# PE0024.net
KiCad netlist of a schematic drawn in Altium Designer
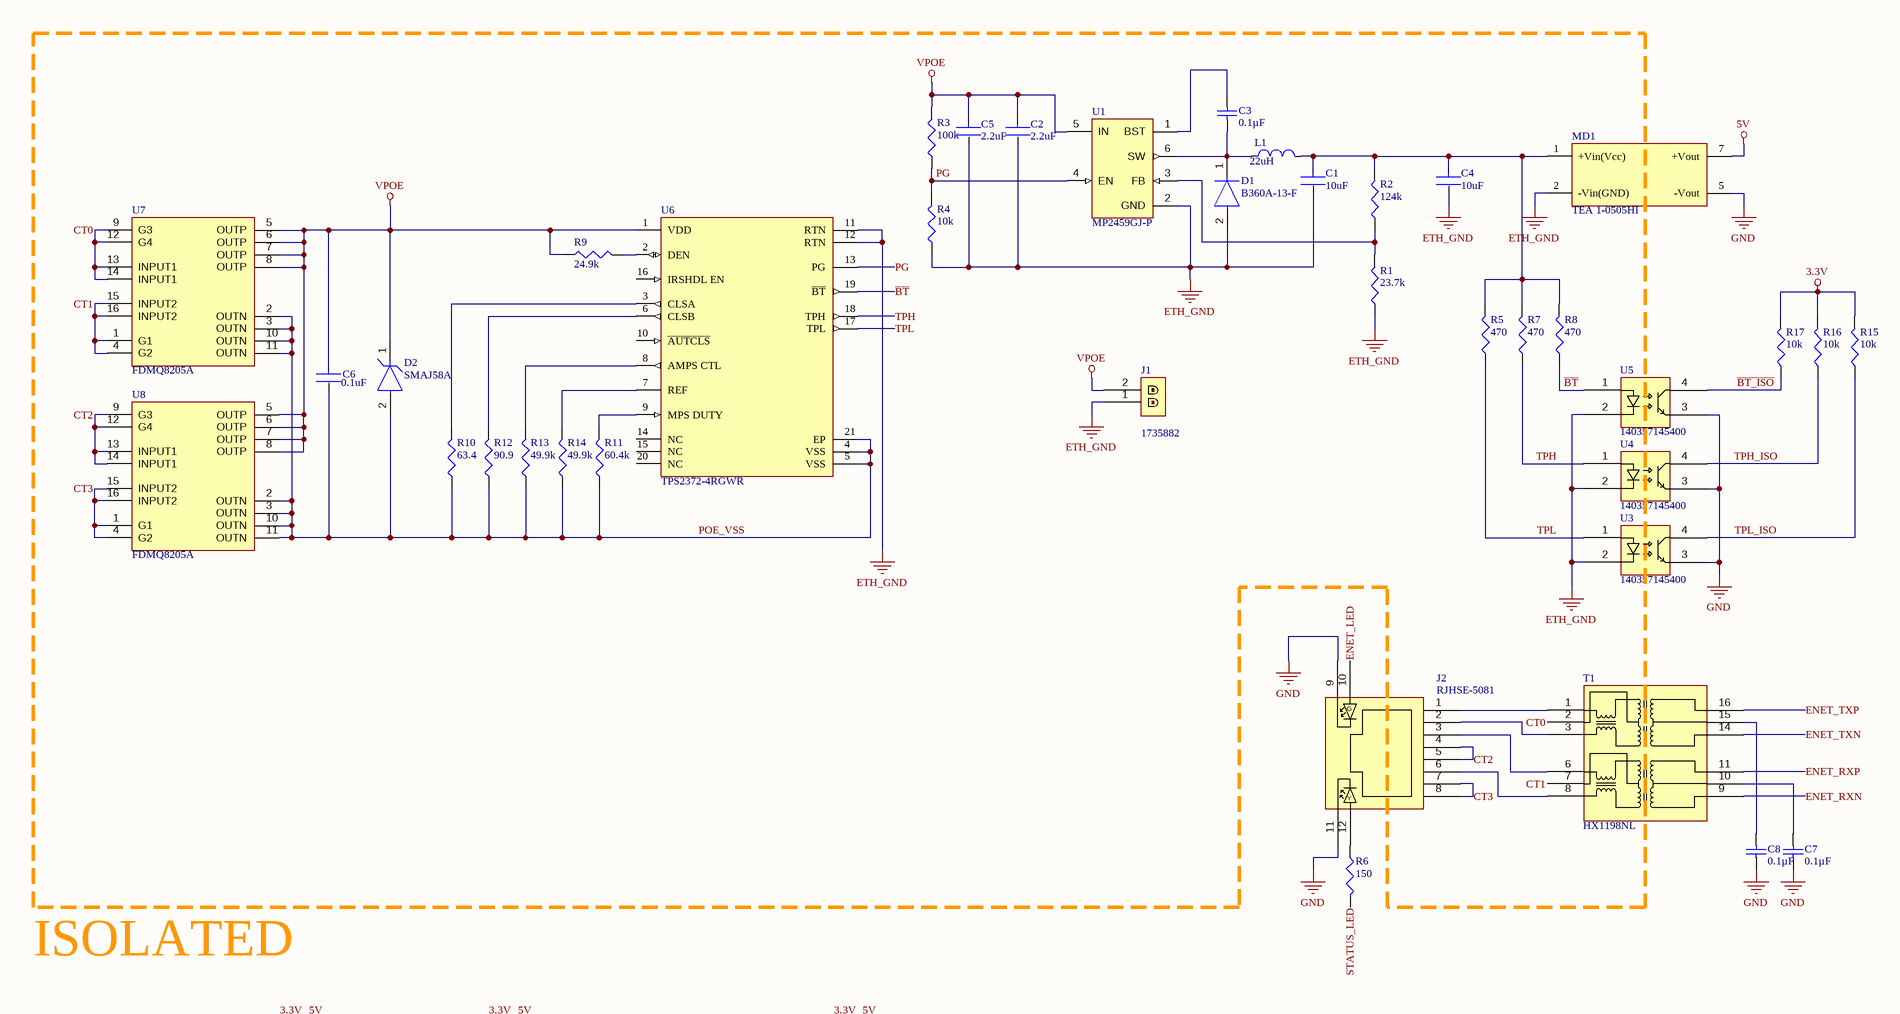
[diagram p0: PE0024.SchDoc, top left]
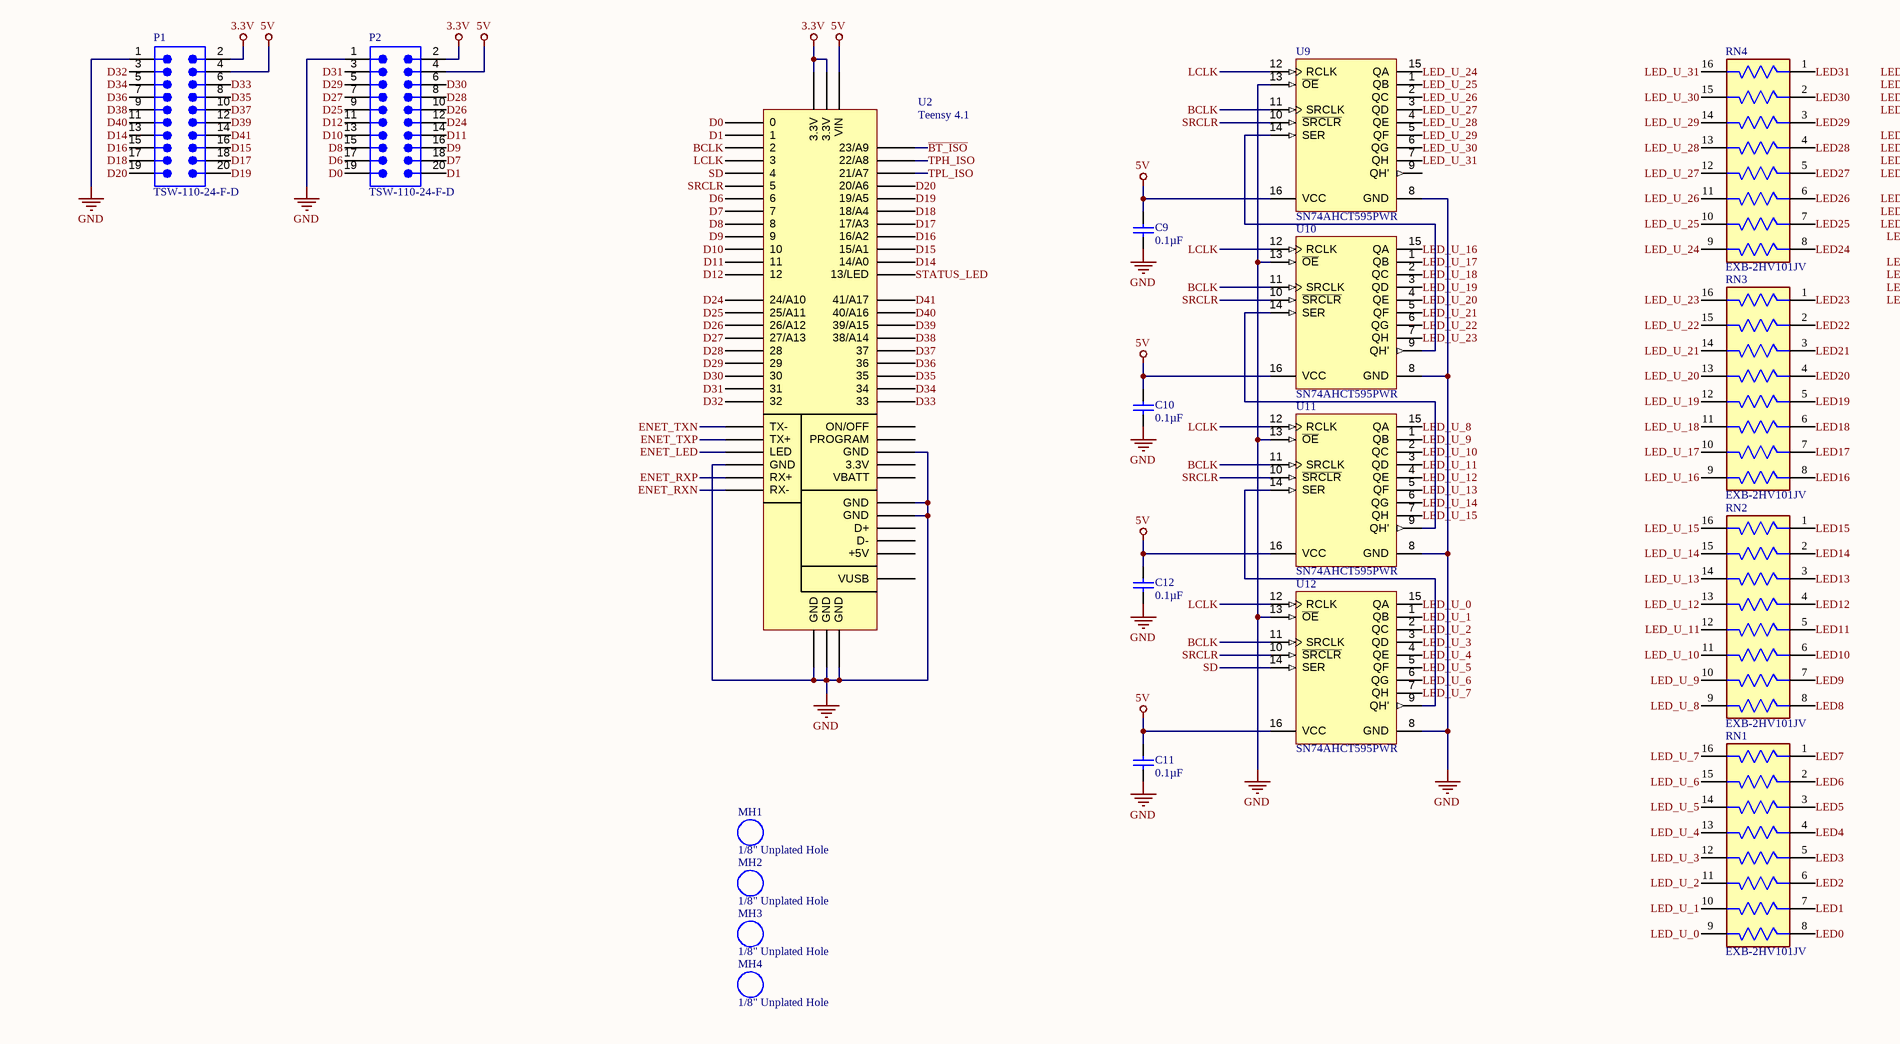
[diagram p1: PE0024.SchDoc, bottom left]
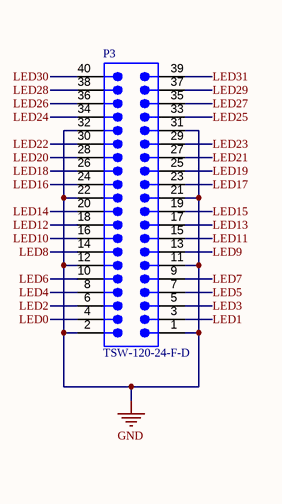
[diagram p2: PE0024.SchDoc, bottom right]

(export (version "E")
  (design (tool "Eeschema 10.0.6"))
  (components
    (comp (ref "C1")
      (value "GRM21BR61C106KE15L")
      (footprint "FP-GRM21B-0_1-IPC_C")
      (description "Chip Multilayer Ceramic Capacitors for General Purpose, 0805, 10uF, X5R, 15%, 10%, 16V")
      (fields
        (field (name "TOLERANCE") "10%")
        (field (name "VOLTAGE") "16V")
        (field (name "CAPACITANCE") "10uF")
      )
      (libsource (lib "Altium Content Vault") (part "b4654b650e69147ec39a6b967a45e02"))
    )
    (comp (ref "C2")
      (value "C3216X7S2A225K160AB")
      (footprint "FP-C3216-160-0_2-IPC_B")
      (description "Multilayer Ceramic Capacitors 2.2uF ±10% 100V X7S SMD 1206")
      (fields
        (field (name "TOLERANCE") "10%")
        (field (name "CAPACITANCE") "2.2uF")
        (field (name "VOLTAGE") "100V")
      )
      (libsource (lib "Altium Content Vault") (part "11868f565c42a9108669ba33697ecf6"))
    )
    (comp (ref "C3")
      (value "0.1µF")
      (footprint "0402CAP")
      (description "CAP CER 0.1UF 50V X7S 0402")
      (fields
        (field (name "PART NUMBER") "CAP_MUR_GRM155C71H104JE19D")
        (field (name "MANUFACTURER PART NUMBER") "GRM155C71H104JE19D")
        (field (name "PUBLISHER") "Altium Limited")
      )
      (libsource (lib "muRata_0402$") (part "CAP_MUR_GRM155C71H104JE19D"))
    )
    (comp (ref "C4")
      (value "GRM21BR61C106KE15L")
      (footprint "FP-GRM21B-0_1-IPC_C")
      (description "Chip Multilayer Ceramic Capacitors for General Purpose, 0805, 10uF, X5R, 15%, 10%, 16V")
      (fields
        (field (name "TOLERANCE") "10%")
        (field (name "VOLTAGE") "16V")
        (field (name "CAPACITANCE") "10uF")
      )
      (libsource (lib "Altium Content Vault") (part "b4654b650e69147ec39a6b967a45e02"))
    )
    (comp (ref "C5")
      (value "C3216X7S2A225K160AB")
      (footprint "FP-C3216-160-0_2-IPC_B")
      (description "Multilayer Ceramic Capacitors 2.2uF ±10% 100V X7S SMD 1206")
      (fields
        (field (name "TOLERANCE") "10%")
        (field (name "CAPACITANCE") "2.2uF")
        (field (name "VOLTAGE") "100V")
      )
      (libsource (lib "Altium Content Vault") (part "11868f565c42a9108669ba33697ecf6"))
    )
    (comp (ref "C6")
      (value "GRM188R72A104KA35D")
      (footprint "FP-GRM188-0_1-e0_2_0_5-IPC_B")
      (description "Chip Multilayer Ceramic Capacitors for General Purpose, 0603, 0.10uF, X7R, 15%, 10%, 100V")
      (fields
        (field (name "CAPACITANCE") "0.1uF")
        (field (name "VOLTAGE") "100V")
        (field (name "TOLERANCE") "10%")
      )
      (libsource (lib "Altium Content Vault") (part "11868f565c42a9108669ba33697ecf6"))
    )
    (comp (ref "C7")
      (value "0.1µF")
      (footprint "0402CAP")
      (description "CAP CER 0.1UF 50V X7S 0402")
      (fields
        (field (name "PART NUMBER") "CAP_MUR_GRM155C71H104JE19D")
        (field (name "MANUFACTURER PART NUMBER") "GRM155C71H104JE19D")
        (field (name "PUBLISHER") "Altium Limited")
      )
      (libsource (lib "muRata_0402$") (part "CAP_MUR_GRM155C71H104JE19D"))
    )
    (comp (ref "C8")
      (value "0.1µF")
      (footprint "0402CAP")
      (description "CAP CER 0.1UF 50V X7S 0402")
      (fields
        (field (name "PART NUMBER") "CAP_MUR_GRM155C71H104JE19D")
        (field (name "MANUFACTURER PART NUMBER") "GRM155C71H104JE19D")
        (field (name "PUBLISHER") "Altium Limited")
      )
      (libsource (lib "muRata_0402$") (part "CAP_MUR_GRM155C71H104JE19D"))
    )
    (comp (ref "C9")
      (value "0.1µF")
      (footprint "0402CAP")
      (description "CAP CER 0.1UF 50V X7S 0402")
      (fields
        (field (name "PART NUMBER") "CAP_MUR_GRM155C71H104JE19D")
        (field (name "MANUFACTURER PART NUMBER") "GRM155C71H104JE19D")
        (field (name "PUBLISHER") "Altium Limited")
      )
      (libsource (lib "muRata_0402$") (part "CAP_MUR_GRM155C71H104JE19D"))
    )
    (comp (ref "C10")
      (value "0.1µF")
      (footprint "0402CAP")
      (description "CAP CER 0.1UF 50V X7S 0402")
      (fields
        (field (name "PART NUMBER") "CAP_MUR_GRM155C71H104JE19D")
        (field (name "MANUFACTURER PART NUMBER") "GRM155C71H104JE19D")
        (field (name "PUBLISHER") "Altium Limited")
      )
      (libsource (lib "muRata_0402$") (part "CAP_MUR_GRM155C71H104JE19D"))
    )
    (comp (ref "C11")
      (value "0.1µF")
      (footprint "0402CAP")
      (description "CAP CER 0.1UF 50V X7S 0402")
      (fields
        (field (name "PART NUMBER") "CAP_MUR_GRM155C71H104JE19D")
        (field (name "MANUFACTURER PART NUMBER") "GRM155C71H104JE19D")
        (field (name "PUBLISHER") "Altium Limited")
      )
      (libsource (lib "muRata_0402$") (part "CAP_MUR_GRM155C71H104JE19D"))
    )
    (comp (ref "C12")
      (value "0.1µF")
      (footprint "0402CAP")
      (description "CAP CER 0.1UF 50V X7S 0402")
      (fields
        (field (name "PART NUMBER") "CAP_MUR_GRM155C71H104JE19D")
        (field (name "MANUFACTURER PART NUMBER") "GRM155C71H104JE19D")
        (field (name "PUBLISHER") "Altium Limited")
      )
      (libsource (lib "muRata_0402$") (part "CAP_MUR_GRM155C71H104JE19D"))
    )
    (comp (ref "D1")
      (value "B360A-13-F")
      (footprint "FP-SMA-MFG")
      (description "DIODE SCHOTTKY 60V 3A SMA")
      (libsource (lib "Altium Content Vault") (part "d7152d700b627762746794eb795d46e"))
    )
    (comp (ref "D2")
      (value "SMAJ58A")
      (footprint "FP-SMAJ-MFG")
      (description "TVS DIODE 58V 93.6V DO214AC")
      (fields (field (name "VOLTAGE") "58V"))
      (libsource (lib "Altium Content Vault") (part "f813f71cba58e380607f5dd3caf9714"))
    )
    (comp (ref "J1")
      (value "1735882")
      (footprint "MSTBW 2,5/2-G-5,08")
      (description "Pluggable Terminal Blocks 2 Pos 5.08mm pitch Through Hole Header")
      (fields
        (field (name "MANUFACTURER") "Phoenix Contact")
        (field (name "VOLTAGE") "300V")
        (field (name "MANUFACTURER PART NUMBER") "1735882")
      )
      (libsource (lib "RDS") (part "1735882"))
    )
    (comp (ref "J2")
      (value "RJHSE-5081")
      (footprint "RDS:RJHSE-5081")
      (description "Modular Jack - Right Angle, Input Output Connectors 8P8C, RA, Without Shield, With LEDs.")
      (fields (field (name "MANUFACTURER") "Amphenol") (field (name "MANUFACTURER PART NUMBER") "RJHSE-5081"))
      (libsource (lib "RDS") (part "RJHSE-5081"))
    )
    (comp (ref "L1")
      (value "NRS6028T220MMGJ")
      (footprint "FP-NR6028-MFG")
      (description "SMD Power Inductors 22uH ±20% 1.3A 0.1755Ω")
      (fields (field (name "INDUCTANCE") "22uH") (field (name "TOLERANCE") "20%"))
      (libsource (lib "Altium Content Vault") (part "725321dda6339637d4d059423bc1c3c"))
    )
    (comp (ref "MD1")
      (value "TEA 1-0505HI")
      (footprint "FP-TEA_1HI-MFG")
      (description "DC DC CONVERTER 5V 1W")
      (libsource (lib "Altium Content Vault") (part "4f7ce3a56b2658afe72e2cdf5ebd808"))
    )
    (comp (ref "MH1")
      (value "1/8\" Unplated Hole")
      (footprint "1/8\" Unplated Hole")
      (libsource (lib "RDS") (part "1/8{dblquote} Unplated Hole"))
    )
    (comp (ref "MH2")
      (value "1/8\" Unplated Hole")
      (footprint "1/8\" Unplated Hole")
      (libsource (lib "RDS") (part "1/8{dblquote} Unplated Hole"))
    )
    (comp (ref "MH3")
      (value "1/8\" Unplated Hole")
      (footprint "1/8\" Unplated Hole")
      (libsource (lib "RDS") (part "1/8{dblquote} Unplated Hole"))
    )
    (comp (ref "MH4")
      (value "1/8\" Unplated Hole")
      (footprint "1/8\" Unplated Hole")
      (libsource (lib "RDS") (part "1/8{dblquote} Unplated Hole"))
    )
    (comp (ref "P1")
      (value "TSW-110-24-F-D")
      (footprint "SMTC-TSW-110-24-X-D")
      (description "0.025\" SQ Post Header, Through-hole, Vertical, -55 to 125 degC, 2.54 mm Pitch, 20-Pin, Male, RoHS")
      (fields (field (name "MANUFACTURER") "Samtec"))
      (libsource (lib "RDS") (part "CMP-1024-00453-1"))
    )
    (comp (ref "P2")
      (value "TSW-110-24-F-D")
      (footprint "SMTC-TSW-110-24-X-D")
      (description "0.025\" SQ Post Header, Through-hole, Vertical, -55 to 125 degC, 2.54 mm Pitch, 20-Pin, Male, RoHS")
      (fields (field (name "MANUFACTURER") "Samtec"))
      (libsource (lib "RDS") (part "CMP-1024-00453-1"))
    )
    (comp (ref "P3")
      (value "TSW-120-24-F-D")
      (footprint "SMTC-TSW-120-24-X-D")
      (description "0.025\" SQ Post Header, Through-hole, Vertical, -55 to 125 degC, 2.54 mm Pitch, 40-Pin, Male, RoHS")
      (fields (field (name "MANUFACTURER") "Samtec"))
      (libsource (lib "Altium Content Vault") (part "SMTC-TSW-120-X-X-D-X"))
    )
    (comp (ref "R1")
      (value "23.7k")
      (footprint "0402RES")
      (description "RES SMD 23.7K OHM 1% 1/10W 0402")
      (fields
        (field (name "PART NUMBER") "RES_PAN_ERJ-2RKF2372X")
        (field (name "MANUFACTURER PART NUMBER") "ERJ-2RKF2372X")
        (field (name "PUBLISHER") "Altium Limited")
      )
      (libsource (lib "ERJ-2RKF$") (part "RES_PAN_ERJ-2RKF2372X"))
    )
    (comp (ref "R2")
      (value "124k")
      (footprint "0402RES")
      (description "RES SMD 124K OHM 1% 1/10W 0402")
      (fields
        (field (name "PART NUMBER") "RES_PAN_ERJ-2RKF1243X")
        (field (name "MANUFACTURER PART NUMBER") "ERJ-2RKF1243X")
        (field (name "PUBLISHER") "Altium Limited")
      )
      (libsource (lib "ERJ-2RKF$") (part "RES_PAN_ERJ-2RKF1243X"))
    )
    (comp (ref "R3")
      (value "100k")
      (footprint "0402RES")
      (description "RES SMD 100K OHM 1% 1/10W 0402")
      (fields
        (field (name "PART NUMBER") "RES_PAN_ERJ-2RKF1003X")
        (field (name "MANUFACTURER PART NUMBER") "ERJ-2RKF1003X")
        (field (name "PUBLISHER") "Altium Limited")
      )
      (libsource (lib "ERJ-2RKF$") (part "RES_PAN_ERJ-2RKF1003X"))
    )
    (comp (ref "R4")
      (value "10k")
      (footprint "0402RES")
      (description "RES SMD 10K OHM 1% 1/10W 0402")
      (fields
        (field (name "PART NUMBER") "RES_PAN_ERJ-2RKF1002X")
        (field (name "MANUFACTURER PART NUMBER") "ERJ-2RKF1002X")
        (field (name "PUBLISHER") "Altium Limited")
      )
      (libsource (lib "ERJ-2RKF$") (part "RES_PAN_ERJ-2RKF1002X"))
    )
    (comp (ref "R5")
      (value "470")
      (footprint "0402RES")
      (description "RES SMD 470 OHM 1% 1/10W 0402")
      (fields
        (field (name "PART NUMBER") "RES_PAN_ERJ-2RKF4700X")
        (field (name "MANUFACTURER PART NUMBER") "ERJ-2RKF4700X")
        (field (name "PUBLISHER") "Altium Limited")
      )
      (libsource (lib "ERJ-2RKF$") (part "RES_PAN_ERJ-2RKF4700X"))
    )
    (comp (ref "R6")
      (value "150")
      (footprint "0402RES")
      (description "RES SMD 150 OHM 1% 1/10W 0402")
      (fields
        (field (name "PART NUMBER") "RES_PAN_ERJ-2RKF1500X")
        (field (name "MANUFACTURER PART NUMBER") "ERJ-2RKF1500X")
        (field (name "PUBLISHER") "Altium Limited")
      )
      (libsource (lib "ERJ-2RKF$") (part "RES_PAN_ERJ-2RKF1500X"))
    )
    (comp (ref "R7")
      (value "470")
      (footprint "0402RES")
      (description "RES SMD 470 OHM 1% 1/10W 0402")
      (fields
        (field (name "PART NUMBER") "RES_PAN_ERJ-2RKF4700X")
        (field (name "MANUFACTURER PART NUMBER") "ERJ-2RKF4700X")
        (field (name "PUBLISHER") "Altium Limited")
      )
      (libsource (lib "ERJ-2RKF$") (part "RES_PAN_ERJ-2RKF4700X"))
    )
    (comp (ref "R8")
      (value "470")
      (footprint "0402RES")
      (description "RES SMD 470 OHM 1% 1/10W 0402")
      (fields
        (field (name "PART NUMBER") "RES_PAN_ERJ-2RKF4700X")
        (field (name "MANUFACTURER PART NUMBER") "ERJ-2RKF4700X")
        (field (name "PUBLISHER") "Altium Limited")
      )
      (libsource (lib "ERJ-2RKF$") (part "RES_PAN_ERJ-2RKF4700X"))
    )
    (comp (ref "R9")
      (value "24.9k")
      (footprint "0402RES")
      (description "RES SMD 24.9K OHM 1% 1/10W 0402")
      (fields
        (field (name "PART NUMBER") "RES_PAN_ERJ-2RKF2492X")
        (field (name "MANUFACTURER PART NUMBER") "ERJ-2RKF2492X")
        (field (name "PUBLISHER") "Altium Limited")
      )
      (libsource (lib "ERJ-2RKF$") (part "RES_PAN_ERJ-2RKF2492X"))
    )
    (comp (ref "R10")
      (value "63.4")
      (footprint "0402RES")
      (description "RES SMD 63.4 OHM 1% 1/10W 0402")
      (fields
        (field (name "PART NUMBER") "RES_PAN_ERJ-2RKF63R4X")
        (field (name "MANUFACTURER PART NUMBER") "ERJ-2RKF63R4X")
        (field (name "PUBLISHER") "Altium Limited")
      )
      (libsource (lib "ERJ-2RKF$") (part "RES_PAN_ERJ-2RKF63R4X"))
    )
    (comp (ref "R11")
      (value "60.4k")
      (footprint "0402RES")
      (description "RES SMD 60.4K OHM 1% 1/10W 0402")
      (fields
        (field (name "PART NUMBER") "RES_PAN_ERJ-2RKF6042X")
        (field (name "MANUFACTURER PART NUMBER") "ERJ-2RKF6042X")
        (field (name "PUBLISHER") "Altium Limited")
      )
      (libsource (lib "ERJ-2RKF$") (part "RES_PAN_ERJ-2RKF6042X"))
    )
    (comp (ref "R12")
      (value "90.9")
      (footprint "0402RES")
      (description "RES SMD 90.9 OHM 1% 1/10W 0402")
      (fields
        (field (name "PART NUMBER") "RES_PAN_ERJ-2RKF90R9X")
        (field (name "MANUFACTURER PART NUMBER") "ERJ-2RKF90R9X")
        (field (name "PUBLISHER") "Altium Limited")
      )
      (libsource (lib "ERJ-2RKF$") (part "RES_PAN_ERJ-2RKF90R9X"))
    )
    (comp (ref "R13")
      (value "49.9k")
      (footprint "0402RES")
      (description "RES SMD 49.9K OHM 1% 1/10W 0402")
      (fields
        (field (name "PART NUMBER") "RES_PAN_ERJ-2RKF4992X")
        (field (name "MANUFACTURER PART NUMBER") "ERJ-2RKF4992X")
        (field (name "PUBLISHER") "Altium Limited")
      )
      (libsource (lib "ERJ-2RKF$") (part "RES_PAN_ERJ-2RKF4992X"))
    )
    (comp (ref "R14")
      (value "49.9k")
      (footprint "0402RES")
      (description "RES SMD 49.9K OHM 1% 1/10W 0402")
      (fields
        (field (name "PART NUMBER") "RES_PAN_ERJ-2RKF4992X")
        (field (name "MANUFACTURER PART NUMBER") "ERJ-2RKF4992X")
        (field (name "PUBLISHER") "Altium Limited")
      )
      (libsource (lib "ERJ-2RKF$") (part "RES_PAN_ERJ-2RKF4992X"))
    )
    (comp (ref "R15")
      (value "10k")
      (footprint "0402RES")
      (description "RES SMD 10K OHM 1% 1/10W 0402")
      (fields
        (field (name "PART NUMBER") "RES_PAN_ERJ-2RKF1002X")
        (field (name "MANUFACTURER PART NUMBER") "ERJ-2RKF1002X")
        (field (name "PUBLISHER") "Altium Limited")
      )
      (libsource (lib "ERJ-2RKF$") (part "RES_PAN_ERJ-2RKF1002X"))
    )
    (comp (ref "R16")
      (value "10k")
      (footprint "0402RES")
      (description "RES SMD 10K OHM 1% 1/10W 0402")
      (fields
        (field (name "PART NUMBER") "RES_PAN_ERJ-2RKF1002X")
        (field (name "MANUFACTURER PART NUMBER") "ERJ-2RKF1002X")
        (field (name "PUBLISHER") "Altium Limited")
      )
      (libsource (lib "ERJ-2RKF$") (part "RES_PAN_ERJ-2RKF1002X"))
    )
    (comp (ref "R17")
      (value "10k")
      (footprint "0402RES")
      (description "RES SMD 10K OHM 1% 1/10W 0402")
      (fields
        (field (name "PART NUMBER") "RES_PAN_ERJ-2RKF1002X")
        (field (name "MANUFACTURER PART NUMBER") "ERJ-2RKF1002X")
        (field (name "PUBLISHER") "Altium Limited")
      )
      (libsource (lib "ERJ-2RKF$") (part "RES_PAN_ERJ-2RKF1002X"))
    )
    (comp (ref "RN1")
      (value "EXB-2HV101JV")
      (footprint "FP-EXB2HV-MFG")
      (description "RES ARRAY 8 RES 100 OHM 1506")
      (fields (field (name "TOLERANCE") "5%"))
      (libsource (lib "Altium Content Vault") (part "42159c3963beb1554014d4041102c8c"))
    )
    (comp (ref "RN2")
      (value "EXB-2HV101JV")
      (footprint "FP-EXB2HV-MFG")
      (description "RES ARRAY 8 RES 100 OHM 1506")
      (fields (field (name "TOLERANCE") "5%"))
      (libsource (lib "Altium Content Vault") (part "42159c3963beb1554014d4041102c8c"))
    )
    (comp (ref "RN3")
      (value "EXB-2HV101JV")
      (footprint "FP-EXB2HV-MFG")
      (description "RES ARRAY 8 RES 100 OHM 1506")
      (fields (field (name "TOLERANCE") "5%"))
      (libsource (lib "Altium Content Vault") (part "42159c3963beb1554014d4041102c8c"))
    )
    (comp (ref "RN4")
      (value "EXB-2HV101JV")
      (footprint "FP-EXB2HV-MFG")
      (description "RES ARRAY 8 RES 100 OHM 1506")
      (fields (field (name "TOLERANCE") "5%"))
      (libsource (lib "Altium Content Vault") (part "42159c3963beb1554014d4041102c8c"))
    )
    (comp (ref "T1")
      (value "HX1198NL")
      (footprint "HX1198NL")
      (description "Telecom Transformer 1: 1/1: 1 1500Vrms -1dB Surface Mount")
      (fields (field (name "MANUFACTURER") "Pulse") (field (name "MANUFACTURER PART NUMBER") "HX1198NL"))
      (libsource (lib "RDS") (part "HX1198NL"))
    )
    (comp (ref "U1")
      (value "MP2459GJ-P")
      (footprint "FP-MP2459GJ-P-MFG")
      (description "IC REG BUCK ADJ 500MA TSOT23-6")
      (fields
        (field (name "OCTOPART") "https://octopart.com/mp2459gj-p-monolithic+power+systems-29216401")
        (field (name "MANUFACTURER") "Monolithic Power Systems")
      )
      (libsource (lib "Altium Content Vault") (part "f46146291308c77894d9fa4073619bb"))
    )
    (comp (ref "U2")
      (value "Teensy 4.1")
      (footprint "Teensy_4.1")
      (description "Teensy 4.1 Development Board")
      (fields (field (name "MANUFACTURER") "SparkFun") (field (name "MANUFACTURER PART NUMBER") "DEV-16771"))
      (libsource (lib "RDS") (part "Teensy 4.1"))
    )
    (comp (ref "U3")
      (value "140357145400")
      (footprint "SOP254P700X210-4N")
      (description "Optocoupler, Transistor, 35V, Sop-4 Rohs Compliant: Yes")
      (fields
        (field (name "MANUFACTURER") "Wurth Electronics")
        (field (name "MANUFACTURER PART NUMBER") "140357145400")
      )
      (libsource (lib "RDS") (part "140357145400"))
    )
    (comp (ref "U4")
      (value "140357145400")
      (footprint "SOP254P700X210-4N")
      (description "Optocoupler, Transistor, 35V, Sop-4 Rohs Compliant: Yes")
      (fields
        (field (name "MANUFACTURER") "Wurth Electronics")
        (field (name "MANUFACTURER PART NUMBER") "140357145400")
      )
      (libsource (lib "RDS") (part "140357145400"))
    )
    (comp (ref "U5")
      (value "140357145400")
      (footprint "SOP254P700X210-4N")
      (description "Optocoupler, Transistor, 35V, Sop-4 Rohs Compliant: Yes")
      (fields
        (field (name "MANUFACTURER") "Wurth Electronics")
        (field (name "MANUFACTURER PART NUMBER") "140357145400")
      )
      (libsource (lib "RDS") (part "140357145400"))
    )
    (comp (ref "U6")
      (value "TPS2372-4RGWR")
      (footprint "FP-RGW0020B-MFG")
      (description "IC POE CNTRL 1 CHANNEL 20VQFN")
      (libsource (lib "Altium Content Vault") (part "0abb89902859fb27db2e32b727076aa"))
    )
    (comp (ref "U7")
      (value "FDMQ8205A")
      (footprint "FP-511CS-MFG")
      (description "GREENBRIDGETM 2 SERIES OF HIGH-E")
      (fields
        (field (name "OCTOPART") "https://octopart.com/fdmq8205a-on+semiconductor-84326195")
        (field (name "MANUFACTURER") "ON Semiconductor")
      )
      (libsource (lib "Altium Content Vault") (part "2abdffca6a3f98fe7701ae5d1e395bd"))
    )
    (comp (ref "U8")
      (value "FDMQ8205A")
      (footprint "FP-511CS-MFG")
      (description "GREENBRIDGETM 2 SERIES OF HIGH-E")
      (fields
        (field (name "OCTOPART") "https://octopart.com/fdmq8205a-on+semiconductor-84326195")
        (field (name "MANUFACTURER") "ON Semiconductor")
      )
      (libsource (lib "Altium Content Vault") (part "2abdffca6a3f98fe7701ae5d1e395bd"))
    )
    (comp (ref "U9")
      (value "SN74AHCT595PWR")
      (footprint "PW0016A_M")
      (description "8-Bit Shift Registers With 3-State Output Registers, PW0016A, LARGE T&R")
      (fields
        (field (name "GENERIC PART NUMBER") "SN74AHCT595")
        (field (name "MANUFACTURER") "Texas Instruments")
      )
      (libsource (lib "Altium Content Vault") (part "TI-SN74AHCT595-PW0016A-16"))
    )
    (comp (ref "U10")
      (value "SN74AHCT595PWR")
      (footprint "PW0016A_M")
      (description "8-Bit Shift Registers With 3-State Output Registers, PW0016A, LARGE T&R")
      (fields
        (field (name "GENERIC PART NUMBER") "SN74AHCT595")
        (field (name "MANUFACTURER") "Texas Instruments")
      )
      (libsource (lib "Altium Content Vault") (part "TI-SN74AHCT595-PW0016A-16"))
    )
    (comp (ref "U11")
      (value "SN74AHCT595PWR")
      (footprint "PW0016A_M")
      (description "8-Bit Shift Registers With 3-State Output Registers, PW0016A, LARGE T&R")
      (fields
        (field (name "GENERIC PART NUMBER") "SN74AHCT595")
        (field (name "MANUFACTURER") "Texas Instruments")
      )
      (libsource (lib "Altium Content Vault") (part "TI-SN74AHCT595-PW0016A-16"))
    )
    (comp (ref "U12")
      (value "SN74AHCT595PWR")
      (footprint "PW0016A_M")
      (description "8-Bit Shift Registers With 3-State Output Registers, PW0016A, LARGE T&R")
      (fields
        (field (name "GENERIC PART NUMBER") "SN74AHCT595")
        (field (name "MANUFACTURER") "Texas Instruments")
      )
      (libsource (lib "Altium Content Vault") (part "TI-SN74AHCT595-PW0016A-16"))
    )
  )
  (nets
    (net (code "1") (name "/BCLK") (class "Default")
      (node (ref "U10") (pin "11") (pinfunction "SRCLK_11") (pintype "input"))
      (node (ref "U11") (pin "11") (pinfunction "SRCLK_11") (pintype "input"))
      (node (ref "U12") (pin "11") (pinfunction "SRCLK_11") (pintype "input"))
      (node (ref "U2") (pin "4") (pinfunction "2_4") (pintype "passive"))
      (node (ref "U9") (pin "11") (pinfunction "SRCLK_11") (pintype "input"))
    )
    (net (code "2") (name "/CT0") (class "Default")
      (node (ref "T1") (pin "2") (pintype "passive"))
      (node (ref "U7") (pin "12") (pinfunction "G4_12") (pintype "passive"))
      (node (ref "U7") (pin "13") (pinfunction "INPUT1_13") (pintype "passive"))
      (node (ref "U7") (pin "14") (pinfunction "INPUT1_14") (pintype "passive"))
      (node (ref "U7") (pin "9") (pinfunction "G3_9") (pintype "passive"))
    )
    (net (code "3") (name "/CT1") (class "Default")
      (node (ref "T1") (pin "7") (pintype "passive"))
      (node (ref "U7") (pin "1") (pinfunction "G1_1") (pintype "passive"))
      (node (ref "U7") (pin "15") (pinfunction "INPUT2_15") (pintype "passive"))
      (node (ref "U7") (pin "16") (pinfunction "INPUT2_16") (pintype "passive"))
      (node (ref "U7") (pin "4") (pinfunction "G2_4") (pintype "passive"))
    )
    (net (code "4") (name "/CT2") (class "Default")
      (node (ref "J2") (pin "4") (pintype "passive"))
      (node (ref "J2") (pin "5") (pintype "passive"))
      (node (ref "U8") (pin "12") (pinfunction "G4_12") (pintype "passive"))
      (node (ref "U8") (pin "13") (pinfunction "INPUT1_13") (pintype "passive"))
      (node (ref "U8") (pin "14") (pinfunction "INPUT1_14") (pintype "passive"))
      (node (ref "U8") (pin "9") (pinfunction "G3_9") (pintype "passive"))
    )
    (net (code "5") (name "/CT3") (class "Default")
      (node (ref "J2") (pin "7") (pintype "passive"))
      (node (ref "J2") (pin "8") (pintype "passive"))
      (node (ref "U8") (pin "1") (pinfunction "G1_1") (pintype "passive"))
      (node (ref "U8") (pin "15") (pinfunction "INPUT2_15") (pintype "passive"))
      (node (ref "U8") (pin "16") (pinfunction "INPUT2_16") (pintype "passive"))
      (node (ref "U8") (pin "4") (pinfunction "G2_4") (pintype "passive"))
    )
    (net (code "6") (name "/D0") (class "Default")
      (node (ref "P2") (pin "19") (pinfunction "19_19") (pintype "passive"))
      (node (ref "U2") (pin "2") (pinfunction "0_2") (pintype "passive"))
    )
    (net (code "7") (name "/D1") (class "Default")
      (node (ref "P2") (pin "20") (pinfunction "20_20") (pintype "passive"))
      (node (ref "U2") (pin "3") (pinfunction "1_3") (pintype "passive"))
    )
    (net (code "8") (name "/D6") (class "Default")
      (node (ref "P2") (pin "17") (pinfunction "17_17") (pintype "passive"))
      (node (ref "U2") (pin "8") (pinfunction "6_8") (pintype "passive"))
    )
    (net (code "9") (name "/D7") (class "Default")
      (node (ref "P2") (pin "18") (pinfunction "18_18") (pintype "passive"))
      (node (ref "U2") (pin "9") (pinfunction "7_9") (pintype "passive"))
    )
    (net (code "10") (name "/D8") (class "Default")
      (node (ref "P2") (pin "15") (pinfunction "15_15") (pintype "passive"))
      (node (ref "U2") (pin "10") (pinfunction "8_10") (pintype "passive"))
    )
    (net (code "11") (name "/D9") (class "Default")
      (node (ref "P2") (pin "16") (pinfunction "16_16") (pintype "passive"))
      (node (ref "U2") (pin "11") (pinfunction "9_11") (pintype "passive"))
    )
    (net (code "12") (name "/D10") (class "Default")
      (node (ref "P2") (pin "13") (pinfunction "13_13") (pintype "passive"))
      (node (ref "U2") (pin "12") (pinfunction "10_12") (pintype "passive"))
    )
    (net (code "13") (name "/D11") (class "Default")
      (node (ref "P2") (pin "14") (pinfunction "14_14") (pintype "passive"))
      (node (ref "U2") (pin "13") (pinfunction "11_13") (pintype "passive"))
    )
    (net (code "14") (name "/D12") (class "Default")
      (node (ref "P2") (pin "11") (pinfunction "11_11") (pintype "passive"))
      (node (ref "U2") (pin "14") (pinfunction "12_14") (pintype "passive"))
    )
    (net (code "15") (name "/D14") (class "Default")
      (node (ref "P1") (pin "13") (pinfunction "13_13") (pintype "passive"))
      (node (ref "U2") (pin "36") (pinfunction "14/A0_36") (pintype "passive"))
    )
    (net (code "16") (name "/D15") (class "Default")
      (node (ref "P1") (pin "16") (pinfunction "16_16") (pintype "passive"))
      (node (ref "U2") (pin "37") (pinfunction "15/A1_37") (pintype "passive"))
    )
    (net (code "17") (name "/D16") (class "Default")
      (node (ref "P1") (pin "15") (pinfunction "15_15") (pintype "passive"))
      (node (ref "U2") (pin "38") (pinfunction "16/A2_38") (pintype "passive"))
    )
    (net (code "18") (name "/D17") (class "Default")
      (node (ref "P1") (pin "18") (pinfunction "18_18") (pintype "passive"))
      (node (ref "U2") (pin "39") (pinfunction "17/A3_39") (pintype "passive"))
    )
    (net (code "19") (name "/D18") (class "Default")
      (node (ref "P1") (pin "17") (pinfunction "17_17") (pintype "passive"))
      (node (ref "U2") (pin "40") (pinfunction "18/A4_40") (pintype "passive"))
    )
    (net (code "20") (name "/D19") (class "Default")
      (node (ref "P1") (pin "20") (pinfunction "20_20") (pintype "passive"))
      (node (ref "U2") (pin "41") (pinfunction "19/A5_41") (pintype "passive"))
    )
    (net (code "21") (name "/D20") (class "Default")
      (node (ref "P1") (pin "19") (pinfunction "19_19") (pintype "passive"))
      (node (ref "U2") (pin "42") (pinfunction "20/A6_42") (pintype "passive"))
    )
    (net (code "22") (name "/D24") (class "Default")
      (node (ref "P2") (pin "12") (pinfunction "12_12") (pintype "passive"))
      (node (ref "U2") (pin "16") (pinfunction "24/A10_16") (pintype "passive"))
    )
    (net (code "23") (name "/D25") (class "Default")
      (node (ref "P2") (pin "9") (pinfunction "9_9") (pintype "passive"))
      (node (ref "U2") (pin "17") (pinfunction "25/A11_17") (pintype "passive"))
    )
    (net (code "24") (name "/D26") (class "Default")
      (node (ref "P2") (pin "10") (pinfunction "10_10") (pintype "passive"))
      (node (ref "U2") (pin "18") (pinfunction "26/A12_18") (pintype "passive"))
    )
    (net (code "25") (name "/D27") (class "Default")
      (node (ref "P2") (pin "7") (pinfunction "7_7") (pintype "passive"))
      (node (ref "U2") (pin "19") (pinfunction "27/A13_19") (pintype "passive"))
    )
    (net (code "26") (name "/D28") (class "Default")
      (node (ref "P2") (pin "8") (pinfunction "8_8") (pintype "passive"))
      (node (ref "U2") (pin "20") (pinfunction "28_20") (pintype "passive"))
    )
    (net (code "27") (name "/D29") (class "Default")
      (node (ref "P2") (pin "5") (pinfunction "5_5") (pintype "passive"))
      (node (ref "U2") (pin "21") (pinfunction "29_21") (pintype "passive"))
    )
    (net (code "28") (name "/D30") (class "Default")
      (node (ref "P2") (pin "6") (pinfunction "6_6") (pintype "passive"))
      (node (ref "U2") (pin "22") (pinfunction "30_22") (pintype "passive"))
    )
    (net (code "29") (name "/D31") (class "Default")
      (node (ref "P2") (pin "3") (pinfunction "3_3") (pintype "passive"))
      (node (ref "U2") (pin "23") (pinfunction "31_23") (pintype "passive"))
    )
    (net (code "30") (name "/D32") (class "Default")
      (node (ref "P1") (pin "3") (pinfunction "3_3") (pintype "passive"))
      (node (ref "U2") (pin "24") (pinfunction "32_24") (pintype "passive"))
    )
    (net (code "31") (name "/D33") (class "Default")
      (node (ref "P1") (pin "6") (pinfunction "6_6") (pintype "passive"))
      (node (ref "U2") (pin "25") (pinfunction "33_25") (pintype "passive"))
    )
    (net (code "32") (name "/D34") (class "Default")
      (node (ref "P1") (pin "5") (pinfunction "5_5") (pintype "passive"))
      (node (ref "U2") (pin "26") (pinfunction "34_26") (pintype "passive"))
    )
    (net (code "33") (name "/D35") (class "Default")
      (node (ref "P1") (pin "8") (pinfunction "8_8") (pintype "passive"))
      (node (ref "U2") (pin "27") (pinfunction "35_27") (pintype "passive"))
    )
    (net (code "34") (name "/D36") (class "Default")
      (node (ref "P1") (pin "7") (pinfunction "7_7") (pintype "passive"))
      (node (ref "U2") (pin "28") (pinfunction "36_28") (pintype "passive"))
    )
    (net (code "35") (name "/D37") (class "Default")
      (node (ref "P1") (pin "10") (pinfunction "10_10") (pintype "passive"))
      (node (ref "U2") (pin "29") (pinfunction "37_29") (pintype "passive"))
    )
    (net (code "36") (name "/D38") (class "Default")
      (node (ref "P1") (pin "9") (pinfunction "9_9") (pintype "passive"))
      (node (ref "U2") (pin "30") (pinfunction "38/A14_30") (pintype "passive"))
    )
    (net (code "37") (name "/D39") (class "Default")
      (node (ref "P1") (pin "12") (pinfunction "12_12") (pintype "passive"))
      (node (ref "U2") (pin "31") (pinfunction "39/A15_31") (pintype "passive"))
    )
    (net (code "38") (name "/D40") (class "Default")
      (node (ref "P1") (pin "11") (pinfunction "11_11") (pintype "passive"))
      (node (ref "U2") (pin "32") (pinfunction "40/A16_32") (pintype "passive"))
    )
    (net (code "39") (name "/D41") (class "Default")
      (node (ref "P1") (pin "14") (pinfunction "14_14") (pintype "passive"))
      (node (ref "U2") (pin "33") (pinfunction "41/A17_33") (pintype "passive"))
    )
    (net (code "40") (name "/ENET_LED") (class "Default")
      (node (ref "J2") (pin "10") (pintype "passive"))
      (node (ref "U2") (pin "62") (pinfunction "LED_62") (pintype "passive"))
    )
    (net (code "41") (name "/ENET_RXN") (class "Default")
      (node (ref "T1") (pin "9") (pintype "passive"))
      (node (ref "U2") (pin "65") (pinfunction "RX-_65") (pintype "passive"))
    )
    (net (code "42") (name "/ENET_RXP") (class "Default")
      (node (ref "T1") (pin "11") (pintype "passive"))
      (node (ref "U2") (pin "64") (pinfunction "RX+_64") (pintype "passive"))
    )
    (net (code "43") (name "/ENET_TXN") (class "Default")
      (node (ref "T1") (pin "14") (pintype "passive"))
      (node (ref "U2") (pin "60") (pinfunction "TX-_60") (pintype "passive"))
    )
    (net (code "44") (name "/ENET_TXP") (class "Default")
      (node (ref "T1") (pin "16") (pintype "passive"))
      (node (ref "U2") (pin "61") (pinfunction "TX+_61") (pintype "passive"))
    )
    (net (code "45") (name "/LCLK") (class "Default")
      (node (ref "U10") (pin "12") (pinfunction "RCLK_12") (pintype "input"))
      (node (ref "U11") (pin "12") (pinfunction "RCLK_12") (pintype "input"))
      (node (ref "U12") (pin "12") (pinfunction "RCLK_12") (pintype "input"))
      (node (ref "U2") (pin "5") (pinfunction "3_5") (pintype "passive"))
      (node (ref "U9") (pin "12") (pinfunction "RCLK_12") (pintype "input"))
    )
    (net (code "46") (name "/LED0") (class "Default")
      (node (ref "P3") (pin "4") (pinfunction "4_4") (pintype "passive"))
      (node (ref "RN1") (pin "8") (pinfunction "8_8") (pintype "passive"))
    )
    (net (code "47") (name "/LED1") (class "Default")
      (node (ref "P3") (pin "3") (pinfunction "3_3") (pintype "passive"))
      (node (ref "RN1") (pin "7") (pinfunction "7_7") (pintype "passive"))
    )
    (net (code "48") (name "/LED2") (class "Default")
      (node (ref "P3") (pin "6") (pinfunction "6_6") (pintype "passive"))
      (node (ref "RN1") (pin "6") (pinfunction "6_6") (pintype "passive"))
    )
    (net (code "49") (name "/LED3") (class "Default")
      (node (ref "P3") (pin "5") (pinfunction "5_5") (pintype "passive"))
      (node (ref "RN1") (pin "5") (pinfunction "5_5") (pintype "passive"))
    )
    (net (code "50") (name "/LED4") (class "Default")
      (node (ref "P3") (pin "8") (pinfunction "8_8") (pintype "passive"))
      (node (ref "RN1") (pin "4") (pinfunction "4_4") (pintype "passive"))
    )
    (net (code "51") (name "/LED5") (class "Default")
      (node (ref "P3") (pin "7") (pinfunction "7_7") (pintype "passive"))
      (node (ref "RN1") (pin "3") (pinfunction "3_3") (pintype "passive"))
    )
    (net (code "52") (name "/LED6") (class "Default")
      (node (ref "P3") (pin "10") (pinfunction "10_10") (pintype "passive"))
      (node (ref "RN1") (pin "2") (pinfunction "2_2") (pintype "passive"))
    )
    (net (code "53") (name "/LED7") (class "Default")
      (node (ref "P3") (pin "9") (pinfunction "9_9") (pintype "passive"))
      (node (ref "RN1") (pin "1") (pinfunction "1_1") (pintype "passive"))
    )
    (net (code "54") (name "/LED8") (class "Default")
      (node (ref "P3") (pin "14") (pinfunction "14_14") (pintype "passive"))
      (node (ref "RN2") (pin "8") (pinfunction "8_8") (pintype "passive"))
    )
    (net (code "55") (name "/LED9") (class "Default")
      (node (ref "P3") (pin "13") (pinfunction "13_13") (pintype "passive"))
      (node (ref "RN2") (pin "7") (pinfunction "7_7") (pintype "passive"))
    )
    (net (code "56") (name "/LED10") (class "Default")
      (node (ref "P3") (pin "16") (pinfunction "16_16") (pintype "passive"))
      (node (ref "RN2") (pin "6") (pinfunction "6_6") (pintype "passive"))
    )
    (net (code "57") (name "/LED11") (class "Default")
      (node (ref "P3") (pin "15") (pinfunction "15_15") (pintype "passive"))
      (node (ref "RN2") (pin "5") (pinfunction "5_5") (pintype "passive"))
    )
    (net (code "58") (name "/LED12") (class "Default")
      (node (ref "P3") (pin "18") (pinfunction "18_18") (pintype "passive"))
      (node (ref "RN2") (pin "4") (pinfunction "4_4") (pintype "passive"))
    )
    (net (code "59") (name "/LED13") (class "Default")
      (node (ref "P3") (pin "17") (pinfunction "17_17") (pintype "passive"))
      (node (ref "RN2") (pin "3") (pinfunction "3_3") (pintype "passive"))
    )
    (net (code "60") (name "/LED14") (class "Default")
      (node (ref "P3") (pin "20") (pinfunction "20_20") (pintype "passive"))
      (node (ref "RN2") (pin "2") (pinfunction "2_2") (pintype "passive"))
    )
    (net (code "61") (name "/LED15") (class "Default")
      (node (ref "P3") (pin "19") (pinfunction "19_19") (pintype "passive"))
      (node (ref "RN2") (pin "1") (pinfunction "1_1") (pintype "passive"))
    )
    (net (code "62") (name "/LED16") (class "Default")
      (node (ref "P3") (pin "24") (pinfunction "24_24") (pintype "passive"))
      (node (ref "RN3") (pin "8") (pinfunction "8_8") (pintype "passive"))
    )
    (net (code "63") (name "/LED17") (class "Default")
      (node (ref "P3") (pin "23") (pinfunction "23_23") (pintype "passive"))
      (node (ref "RN3") (pin "7") (pinfunction "7_7") (pintype "passive"))
    )
    (net (code "64") (name "/LED18") (class "Default")
      (node (ref "P3") (pin "26") (pinfunction "26_26") (pintype "passive"))
      (node (ref "RN3") (pin "6") (pinfunction "6_6") (pintype "passive"))
    )
    (net (code "65") (name "/LED19") (class "Default")
      (node (ref "P3") (pin "25") (pinfunction "25_25") (pintype "passive"))
      (node (ref "RN3") (pin "5") (pinfunction "5_5") (pintype "passive"))
    )
    (net (code "66") (name "/LED20") (class "Default")
      (node (ref "P3") (pin "28") (pinfunction "28_28") (pintype "passive"))
      (node (ref "RN3") (pin "4") (pinfunction "4_4") (pintype "passive"))
    )
    (net (code "67") (name "/LED21") (class "Default")
      (node (ref "P3") (pin "27") (pinfunction "27_27") (pintype "passive"))
      (node (ref "RN3") (pin "3") (pinfunction "3_3") (pintype "passive"))
    )
    (net (code "68") (name "/LED22") (class "Default")
      (node (ref "P3") (pin "30") (pinfunction "30_30") (pintype "passive"))
      (node (ref "RN3") (pin "2") (pinfunction "2_2") (pintype "passive"))
    )
    (net (code "69") (name "/LED23") (class "Default")
      (node (ref "P3") (pin "29") (pinfunction "29_29") (pintype "passive"))
      (node (ref "RN3") (pin "1") (pinfunction "1_1") (pintype "passive"))
    )
    (net (code "70") (name "/LED24") (class "Default")
      (node (ref "P3") (pin "34") (pinfunction "34_34") (pintype "passive"))
      (node (ref "RN4") (pin "8") (pinfunction "8_8") (pintype "passive"))
    )
    (net (code "71") (name "/LED25") (class "Default")
      (node (ref "P3") (pin "33") (pinfunction "33_33") (pintype "passive"))
      (node (ref "RN4") (pin "7") (pinfunction "7_7") (pintype "passive"))
    )
    (net (code "72") (name "/LED26") (class "Default")
      (node (ref "P3") (pin "36") (pinfunction "36_36") (pintype "passive"))
      (node (ref "RN4") (pin "6") (pinfunction "6_6") (pintype "passive"))
    )
    (net (code "73") (name "/LED27") (class "Default")
      (node (ref "P3") (pin "35") (pinfunction "35_35") (pintype "passive"))
      (node (ref "RN4") (pin "5") (pinfunction "5_5") (pintype "passive"))
    )
    (net (code "74") (name "/LED28") (class "Default")
      (node (ref "P3") (pin "38") (pinfunction "38_38") (pintype "passive"))
      (node (ref "RN4") (pin "4") (pinfunction "4_4") (pintype "passive"))
    )
    (net (code "75") (name "/LED29") (class "Default")
      (node (ref "P3") (pin "37") (pinfunction "37_37") (pintype "passive"))
      (node (ref "RN4") (pin "3") (pinfunction "3_3") (pintype "passive"))
    )
    (net (code "76") (name "/LED30") (class "Default")
      (node (ref "P3") (pin "40") (pinfunction "40_40") (pintype "passive"))
      (node (ref "RN4") (pin "2") (pinfunction "2_2") (pintype "passive"))
    )
    (net (code "77") (name "/LED31") (class "Default")
      (node (ref "P3") (pin "39") (pinfunction "39_39") (pintype "passive"))
      (node (ref "RN4") (pin "1") (pinfunction "1_1") (pintype "passive"))
    )
    (net (code "78") (name "/LED_U_0") (class "Default")
      (node (ref "RN1") (pin "9") (pinfunction "9_9") (pintype "passive"))
      (node (ref "U12") (pin "15") (pinfunction "QA_15") (pintype "tri_state"))
    )
    (net (code "79") (name "/LED_U_1") (class "Default")
      (node (ref "RN1") (pin "10") (pinfunction "10_10") (pintype "passive"))
      (node (ref "U12") (pin "1") (pinfunction "QB_1") (pintype "tri_state"))
    )
    (net (code "80") (name "/LED_U_2") (class "Default")
      (node (ref "RN1") (pin "11") (pinfunction "11_11") (pintype "passive"))
      (node (ref "U12") (pin "2") (pinfunction "QC_2") (pintype "tri_state"))
    )
    (net (code "81") (name "/LED_U_3") (class "Default")
      (node (ref "RN1") (pin "12") (pinfunction "12_12") (pintype "passive"))
      (node (ref "U12") (pin "3") (pinfunction "QD_3") (pintype "tri_state"))
    )
    (net (code "82") (name "/LED_U_4") (class "Default")
      (node (ref "RN1") (pin "13") (pinfunction "13_13") (pintype "passive"))
      (node (ref "U12") (pin "4") (pinfunction "QE_4") (pintype "tri_state"))
    )
    (net (code "83") (name "/LED_U_5") (class "Default")
      (node (ref "RN1") (pin "14") (pinfunction "14_14") (pintype "passive"))
      (node (ref "U12") (pin "5") (pinfunction "QF_5") (pintype "tri_state"))
    )
    (net (code "84") (name "/LED_U_6") (class "Default")
      (node (ref "RN1") (pin "15") (pinfunction "15_15") (pintype "passive"))
      (node (ref "U12") (pin "6") (pinfunction "QG_6") (pintype "tri_state"))
    )
    (net (code "85") (name "/LED_U_7") (class "Default")
      (node (ref "RN1") (pin "16") (pinfunction "16_16") (pintype "passive"))
      (node (ref "U12") (pin "7") (pinfunction "QH_7") (pintype "tri_state"))
    )
    (net (code "86") (name "/LED_U_8") (class "Default")
      (node (ref "RN2") (pin "9") (pinfunction "9_9") (pintype "passive"))
      (node (ref "U11") (pin "15") (pinfunction "QA_15") (pintype "tri_state"))
    )
    (net (code "87") (name "/LED_U_9") (class "Default")
      (node (ref "RN2") (pin "10") (pinfunction "10_10") (pintype "passive"))
      (node (ref "U11") (pin "1") (pinfunction "QB_1") (pintype "tri_state"))
    )
    (net (code "88") (name "/LED_U_10") (class "Default")
      (node (ref "RN2") (pin "11") (pinfunction "11_11") (pintype "passive"))
      (node (ref "U11") (pin "2") (pinfunction "QC_2") (pintype "tri_state"))
    )
    (net (code "89") (name "/LED_U_11") (class "Default")
      (node (ref "RN2") (pin "12") (pinfunction "12_12") (pintype "passive"))
      (node (ref "U11") (pin "3") (pinfunction "QD_3") (pintype "tri_state"))
    )
    (net (code "90") (name "/LED_U_12") (class "Default")
      (node (ref "RN2") (pin "13") (pinfunction "13_13") (pintype "passive"))
      (node (ref "U11") (pin "4") (pinfunction "QE_4") (pintype "tri_state"))
    )
    (net (code "91") (name "/LED_U_13") (class "Default")
      (node (ref "RN2") (pin "14") (pinfunction "14_14") (pintype "passive"))
      (node (ref "U11") (pin "5") (pinfunction "QF_5") (pintype "tri_state"))
    )
    (net (code "92") (name "/LED_U_14") (class "Default")
      (node (ref "RN2") (pin "15") (pinfunction "15_15") (pintype "passive"))
      (node (ref "U11") (pin "6") (pinfunction "QG_6") (pintype "tri_state"))
    )
    (net (code "93") (name "/LED_U_15") (class "Default")
      (node (ref "RN2") (pin "16") (pinfunction "16_16") (pintype "passive"))
      (node (ref "U11") (pin "7") (pinfunction "QH_7") (pintype "tri_state"))
    )
    (net (code "94") (name "/LED_U_16") (class "Default")
      (node (ref "RN3") (pin "9") (pinfunction "9_9") (pintype "passive"))
      (node (ref "U10") (pin "15") (pinfunction "QA_15") (pintype "tri_state"))
    )
    (net (code "95") (name "/LED_U_17") (class "Default")
      (node (ref "RN3") (pin "10") (pinfunction "10_10") (pintype "passive"))
      (node (ref "U10") (pin "1") (pinfunction "QB_1") (pintype "tri_state"))
    )
    (net (code "96") (name "/LED_U_18") (class "Default")
      (node (ref "RN3") (pin "11") (pinfunction "11_11") (pintype "passive"))
      (node (ref "U10") (pin "2") (pinfunction "QC_2") (pintype "tri_state"))
    )
    (net (code "97") (name "/LED_U_19") (class "Default")
      (node (ref "RN3") (pin "12") (pinfunction "12_12") (pintype "passive"))
      (node (ref "U10") (pin "3") (pinfunction "QD_3") (pintype "tri_state"))
    )
    (net (code "98") (name "/LED_U_20") (class "Default")
      (node (ref "RN3") (pin "13") (pinfunction "13_13") (pintype "passive"))
      (node (ref "U10") (pin "4") (pinfunction "QE_4") (pintype "tri_state"))
    )
    (net (code "99") (name "/LED_U_21") (class "Default")
      (node (ref "RN3") (pin "14") (pinfunction "14_14") (pintype "passive"))
      (node (ref "U10") (pin "5") (pinfunction "QF_5") (pintype "tri_state"))
    )
    (net (code "100") (name "/LED_U_22") (class "Default")
      (node (ref "RN3") (pin "15") (pinfunction "15_15") (pintype "passive"))
      (node (ref "U10") (pin "6") (pinfunction "QG_6") (pintype "tri_state"))
    )
    (net (code "101") (name "/LED_U_23") (class "Default")
      (node (ref "RN3") (pin "16") (pinfunction "16_16") (pintype "passive"))
      (node (ref "U10") (pin "7") (pinfunction "QH_7") (pintype "tri_state"))
    )
    (net (code "102") (name "/LED_U_24") (class "Default")
      (node (ref "RN4") (pin "9") (pinfunction "9_9") (pintype "passive"))
      (node (ref "U9") (pin "15") (pinfunction "QA_15") (pintype "tri_state"))
    )
    (net (code "103") (name "/LED_U_25") (class "Default")
      (node (ref "RN4") (pin "10") (pinfunction "10_10") (pintype "passive"))
      (node (ref "U9") (pin "1") (pinfunction "QB_1") (pintype "tri_state"))
    )
    (net (code "104") (name "/LED_U_26") (class "Default")
      (node (ref "RN4") (pin "11") (pinfunction "11_11") (pintype "passive"))
      (node (ref "U9") (pin "2") (pinfunction "QC_2") (pintype "tri_state"))
    )
    (net (code "105") (name "/LED_U_27") (class "Default")
      (node (ref "RN4") (pin "12") (pinfunction "12_12") (pintype "passive"))
      (node (ref "U9") (pin "3") (pinfunction "QD_3") (pintype "tri_state"))
    )
    (net (code "106") (name "/LED_U_28") (class "Default")
      (node (ref "RN4") (pin "13") (pinfunction "13_13") (pintype "passive"))
      (node (ref "U9") (pin "4") (pinfunction "QE_4") (pintype "tri_state"))
    )
    (net (code "107") (name "/LED_U_29") (class "Default")
      (node (ref "RN4") (pin "14") (pinfunction "14_14") (pintype "passive"))
      (node (ref "U9") (pin "5") (pinfunction "QF_5") (pintype "tri_state"))
    )
    (net (code "108") (name "/LED_U_30") (class "Default")
      (node (ref "RN4") (pin "15") (pinfunction "15_15") (pintype "passive"))
      (node (ref "U9") (pin "6") (pinfunction "QG_6") (pintype "tri_state"))
    )
    (net (code "109") (name "/LED_U_31") (class "Default")
      (node (ref "RN4") (pin "16") (pinfunction "16_16") (pintype "passive"))
      (node (ref "U9") (pin "7") (pinfunction "QH_7") (pintype "tri_state"))
    )
    (net (code "110") (name "/PG") (class "Default")
      (node (ref "R3") (pin "1") (pinfunction "1_1") (pintype "passive"))
      (node (ref "R4") (pin "2") (pinfunction "2_2") (pintype "passive"))
      (node (ref "U1") (pin "4") (pinfunction "EN_4") (pintype "input"))
      (node (ref "U6") (pin "13") (pinfunction "PG_13") (pintype "open_collector"))
    )
    (net (code "111") (name "/POE_VSS") (class "Default")
      (node (ref "C6") (pin "2") (pinfunction "2_2") (pintype "passive"))
      (node (ref "D2") (pin "2") (pinfunction "A_2") (pintype "passive"))
      (node (ref "R10") (pin "1") (pinfunction "1_1") (pintype "passive"))
      (node (ref "R11") (pin "1") (pinfunction "1_1") (pintype "passive"))
      (node (ref "R12") (pin "1") (pinfunction "1_1") (pintype "passive"))
      (node (ref "R13") (pin "1") (pinfunction "1_1") (pintype "passive"))
      (node (ref "R14") (pin "1") (pinfunction "1_1") (pintype "passive"))
      (node (ref "U6") (pin "21") (pinfunction "EP_21") (pintype "passive"))
      (node (ref "U6") (pin "4") (pinfunction "VSS_4") (pintype "power_in"))
      (node (ref "U6") (pin "5") (pinfunction "VSS_5") (pintype "power_in"))
      (node (ref "U7") (pin "10") (pinfunction "OUTN_10") (pintype "passive"))
      (node (ref "U7") (pin "11") (pinfunction "OUTN_11") (pintype "passive"))
      (node (ref "U7") (pin "2") (pinfunction "OUTN_2") (pintype "passive"))
      (node (ref "U7") (pin "3") (pinfunction "OUTN_3") (pintype "passive"))
      (node (ref "U8") (pin "10") (pinfunction "OUTN_10") (pintype "passive"))
      (node (ref "U8") (pin "11") (pinfunction "OUTN_11") (pintype "passive"))
      (node (ref "U8") (pin "2") (pinfunction "OUTN_2") (pintype "passive"))
      (node (ref "U8") (pin "3") (pinfunction "OUTN_3") (pintype "passive"))
    )
    (net (code "112") (name "/SD") (class "Default")
      (node (ref "U12") (pin "14") (pinfunction "SER_14") (pintype "input"))
      (node (ref "U2") (pin "6") (pinfunction "4_6") (pintype "passive"))
    )
    (net (code "113") (name "/SRCLR") (class "Default")
      (node (ref "U10") (pin "10") (pinfunction "~{SRCLR}_10") (pintype "input"))
      (node (ref "U11") (pin "10") (pinfunction "~{SRCLR}_10") (pintype "input"))
      (node (ref "U12") (pin "10") (pinfunction "~{SRCLR}_10") (pintype "input"))
      (node (ref "U2") (pin "7") (pinfunction "5_7") (pintype "passive"))
      (node (ref "U9") (pin "10") (pinfunction "~{SRCLR}_10") (pintype "input"))
    )
    (net (code "114") (name "/STATUS_LED") (class "Default")
      (node (ref "R6") (pin "2") (pinfunction "2_2") (pintype "passive"))
      (node (ref "U2") (pin "35") (pinfunction "13/LED_35") (pintype "passive"))
    )
    (net (code "115") (name "/TPH") (class "Default")
      (node (ref "R7") (pin "1") (pinfunction "1_1") (pintype "passive"))
      (node (ref "U4") (pin "1") (pintype "passive"))
      (node (ref "U6") (pin "18") (pinfunction "TPH_18") (pintype "output"))
    )
    (net (code "116") (name "/TPH_ISO") (class "Default")
      (node (ref "R16") (pin "1") (pinfunction "1_1") (pintype "passive"))
      (node (ref "U2") (pin "44") (pinfunction "22/A8_44") (pintype "passive"))
      (node (ref "U4") (pin "4") (pintype "passive"))
    )
    (net (code "117") (name "/TPL") (class "Default")
      (node (ref "R5") (pin "1") (pinfunction "1_1") (pintype "passive"))
      (node (ref "U3") (pin "1") (pintype "passive"))
      (node (ref "U6") (pin "17") (pinfunction "TPL_17") (pintype "output"))
    )
    (net (code "118") (name "/TPL_ISO") (class "Default")
      (node (ref "R15") (pin "1") (pinfunction "1_1") (pintype "passive"))
      (node (ref "U2") (pin "43") (pinfunction "21/A7_43") (pintype "passive"))
      (node (ref "U3") (pin "4") (pintype "passive"))
    )
    (net (code "119") (name "/~{BT_ISO}") (class "Default")
      (node (ref "R17") (pin "1") (pinfunction "1_1") (pintype "passive"))
      (node (ref "U2") (pin "45") (pinfunction "23/A9_45") (pintype "passive"))
      (node (ref "U5") (pin "4") (pintype "passive"))
    )
    (net (code "120") (name "/~{BT}") (class "Default")
      (node (ref "R8") (pin "1") (pinfunction "1_1") (pintype "passive"))
      (node (ref "U5") (pin "1") (pintype "passive"))
      (node (ref "U6") (pin "19") (pinfunction "~{BT}_19") (pintype "output"))
    )
    (net (code "121") (name "3.3V") (class "Default")
      (node (ref "P1") (pin "2") (pinfunction "2_2") (pintype "passive"))
      (node (ref "P2") (pin "2") (pinfunction "2_2") (pintype "passive"))
      (node (ref "R15") (pin "2") (pinfunction "2_2") (pintype "passive"))
      (node (ref "R16") (pin "2") (pinfunction "2_2") (pintype "passive"))
      (node (ref "R17") (pin "2") (pinfunction "2_2") (pintype "passive"))
      (node (ref "U2") (pin "15") (pinfunction "3.3V_15") (pintype "passive"))
      (node (ref "U2") (pin "46") (pinfunction "3.3V_46") (pintype "passive"))
    )
    (net (code "122") (name "5V") (class "Default")
      (node (ref "C10") (pin "2") (pinfunction "2_2") (pintype "passive"))
      (node (ref "C11") (pin "2") (pinfunction "2_2") (pintype "passive"))
      (node (ref "C12") (pin "2") (pinfunction "2_2") (pintype "passive"))
      (node (ref "C9") (pin "2") (pinfunction "2_2") (pintype "passive"))
      (node (ref "MD1") (pin "7") (pinfunction "+Vout_7") (pintype "power_in"))
      (node (ref "P1") (pin "4") (pinfunction "4_4") (pintype "passive"))
      (node (ref "P2") (pin "4") (pinfunction "4_4") (pintype "passive"))
      (node (ref "U10") (pin "16") (pinfunction "VCC_16") (pintype "power_in"))
      (node (ref "U11") (pin "16") (pinfunction "VCC_16") (pintype "power_in"))
      (node (ref "U12") (pin "16") (pinfunction "VCC_16") (pintype "power_in"))
      (node (ref "U2") (pin "48") (pinfunction "VIN_48") (pintype "passive"))
      (node (ref "U9") (pin "16") (pinfunction "VCC_16") (pintype "power_in"))
    )
    (net (code "123") (name "ETH_GND") (class "Default")
      (node (ref "C1") (pin "2") (pinfunction "2_2") (pintype "passive"))
      (node (ref "C2") (pin "2") (pinfunction "2_2") (pintype "passive"))
      (node (ref "C4") (pin "2") (pinfunction "2_2") (pintype "passive"))
      (node (ref "C5") (pin "2") (pinfunction "2_2") (pintype "passive"))
      (node (ref "D1") (pin "2") (pinfunction "A_2") (pintype "passive"))
      (node (ref "J1") (pin "1") (pintype "passive"))
      (node (ref "MD1") (pin "2") (pinfunction "-Vin(GND)_2") (pintype "power_in"))
      (node (ref "R1") (pin "1") (pinfunction "1_1") (pintype "passive"))
      (node (ref "R4") (pin "1") (pinfunction "1_1") (pintype "passive"))
      (node (ref "U1") (pin "2") (pinfunction "GND_2") (pintype "power_in"))
      (node (ref "U3") (pin "2") (pintype "passive"))
      (node (ref "U4") (pin "2") (pintype "passive"))
      (node (ref "U5") (pin "2") (pintype "passive"))
      (node (ref "U6") (pin "11") (pinfunction "RTN_11") (pintype "passive"))
      (node (ref "U6") (pin "12") (pinfunction "RTN_12") (pintype "passive"))
    )
    (net (code "124") (name "GND") (class "Default")
      (node (ref "C10") (pin "1") (pinfunction "1_1") (pintype "passive"))
      (node (ref "C11") (pin "1") (pinfunction "1_1") (pintype "passive"))
      (node (ref "C12") (pin "1") (pinfunction "1_1") (pintype "passive"))
      (node (ref "C7") (pin "1") (pinfunction "1_1") (pintype "passive"))
      (node (ref "C8") (pin "1") (pinfunction "1_1") (pintype "passive"))
      (node (ref "C9") (pin "1") (pinfunction "1_1") (pintype "passive"))
      (node (ref "J2") (pin "11") (pintype "passive"))
      (node (ref "J2") (pin "9") (pintype "passive"))
      (node (ref "MD1") (pin "5") (pinfunction "-Vout_5") (pintype "power_in"))
      (node (ref "P1") (pin "1") (pinfunction "1_1") (pintype "passive"))
      (node (ref "P2") (pin "1") (pinfunction "1_1") (pintype "passive"))
      (node (ref "P3") (pin "1") (pinfunction "1_1") (pintype "passive"))
      (node (ref "P3") (pin "11") (pinfunction "11_11") (pintype "passive"))
      (node (ref "P3") (pin "12") (pinfunction "12_12") (pintype "passive"))
      (node (ref "P3") (pin "2") (pinfunction "2_2") (pintype "passive"))
      (node (ref "P3") (pin "21") (pinfunction "21_21") (pintype "passive"))
      (node (ref "P3") (pin "22") (pinfunction "22_22") (pintype "passive"))
      (node (ref "P3") (pin "31") (pinfunction "31_31") (pintype "passive"))
      (node (ref "P3") (pin "32") (pinfunction "32_32") (pintype "passive"))
      (node (ref "U10") (pin "13") (pinfunction "~{OE}_13") (pintype "input"))
      (node (ref "U10") (pin "8") (pinfunction "GND_8") (pintype "power_in"))
      (node (ref "U11") (pin "13") (pinfunction "~{OE}_13") (pintype "input"))
      (node (ref "U11") (pin "8") (pinfunction "GND_8") (pintype "power_in"))
      (node (ref "U12") (pin "13") (pinfunction "~{OE}_13") (pintype "input"))
      (node (ref "U12") (pin "8") (pinfunction "GND_8") (pintype "power_in"))
      (node (ref "U2") (pin "1") (pinfunction "GND_1") (pintype "passive"))
      (node (ref "U2") (pin "34") (pinfunction "GND_34") (pintype "passive"))
      (node (ref "U2") (pin "47") (pinfunction "GND_47") (pintype "passive"))
      (node (ref "U2") (pin "51") (pinfunction "GND_51") (pintype "passive"))
      (node (ref "U2") (pin "57") (pinfunction "GND_57") (pintype "passive"))
      (node (ref "U2") (pin "58") (pinfunction "GND_58") (pintype "passive"))
      (node (ref "U2") (pin "63") (pinfunction "GND_63") (pintype "passive"))
      (node (ref "U3") (pin "3") (pintype "passive"))
      (node (ref "U4") (pin "3") (pintype "passive"))
      (node (ref "U5") (pin "3") (pintype "passive"))
      (node (ref "U9") (pin "13") (pinfunction "~{OE}_13") (pintype "input"))
      (node (ref "U9") (pin "8") (pinfunction "GND_8") (pintype "power_in"))
    )
    (net (code "125") (name "Net-(C7-Pad2)") (class "Default")
      (node (ref "C7") (pin "2") (pinfunction "2_2") (pintype "passive"))
      (node (ref "T1") (pin "10") (pintype "passive"))
    )
    (net (code "126") (name "Net-(C8-Pad2)") (class "Default")
      (node (ref "C8") (pin "2") (pinfunction "2_2") (pintype "passive"))
      (node (ref "T1") (pin "15") (pintype "passive"))
    )
    (net (code "127") (name "Net-(D1-C)") (class "Default")
      (node (ref "C3") (pin "1") (pinfunction "1_1") (pintype "passive"))
      (node (ref "D1") (pin "1") (pinfunction "C_1") (pintype "passive"))
      (node (ref "L1") (pin "1") (pinfunction "1_1") (pintype "passive"))
      (node (ref "U1") (pin "6") (pinfunction "SW_6") (pintype "output"))
    )
    (net (code "128") (name "Net-(J2-Pad1)") (class "Default")
      (node (ref "J2") (pin "1") (pintype "passive"))
      (node (ref "T1") (pin "1") (pintype "passive"))
    )
    (net (code "129") (name "Net-(J2-Pad2)") (class "Default")
      (node (ref "J2") (pin "2") (pintype "passive"))
      (node (ref "T1") (pin "3") (pintype "passive"))
    )
    (net (code "130") (name "Net-(J2-Pad3)") (class "Default")
      (node (ref "J2") (pin "3") (pintype "passive"))
      (node (ref "T1") (pin "6") (pintype "passive"))
    )
    (net (code "131") (name "Net-(J2-Pad6)") (class "Default")
      (node (ref "J2") (pin "6") (pintype "passive"))
      (node (ref "T1") (pin "8") (pintype "passive"))
    )
    (net (code "132") (name "Net-(J2-Pad12)") (class "Default")
      (node (ref "J2") (pin "12") (pintype "passive"))
      (node (ref "R6") (pin "1") (pinfunction "1_1") (pintype "passive"))
    )
    (net (code "133") (name "Net-(MD1-+Vin(Vcc))") (class "Default")
      (node (ref "C1") (pin "1") (pinfunction "1_1") (pintype "passive"))
      (node (ref "C4") (pin "1") (pinfunction "1_1") (pintype "passive"))
      (node (ref "L1") (pin "2") (pinfunction "2_2") (pintype "passive"))
      (node (ref "MD1") (pin "1") (pinfunction "+Vin(Vcc)_1") (pintype "power_in"))
      (node (ref "R2") (pin "2") (pinfunction "2_2") (pintype "passive"))
      (node (ref "R5") (pin "2") (pinfunction "2_2") (pintype "passive"))
      (node (ref "R7") (pin "2") (pinfunction "2_2") (pintype "passive"))
      (node (ref "R8") (pin "2") (pinfunction "2_2") (pintype "passive"))
    )
    (net (code "134") (name "Net-(U1-BST)") (class "Default")
      (node (ref "C3") (pin "2") (pinfunction "2_2") (pintype "passive"))
      (node (ref "U1") (pin "1") (pinfunction "BST_1") (pintype "passive"))
    )
    (net (code "135") (name "Net-(U1-FB)") (class "Default")
      (node (ref "R1") (pin "2") (pinfunction "2_2") (pintype "passive"))
      (node (ref "R2") (pin "1") (pinfunction "1_1") (pintype "passive"))
      (node (ref "U1") (pin "3") (pinfunction "FB_3") (pintype "input"))
    )
    (net (code "136") (name "Net-(U6-AMPS_CTL)") (class "Default")
      (node (ref "R13") (pin "2") (pinfunction "2_2") (pintype "passive"))
      (node (ref "U6") (pin "8") (pinfunction "AMPS_CTL_8") (pintype "output"))
    )
    (net (code "137") (name "Net-(U6-CLSA)") (class "Default")
      (node (ref "R10") (pin "2") (pinfunction "2_2") (pintype "passive"))
      (node (ref "U6") (pin "3") (pinfunction "CLSA_3") (pintype "output"))
    )
    (net (code "138") (name "Net-(U6-CLSB)") (class "Default")
      (node (ref "R12") (pin "2") (pinfunction "2_2") (pintype "passive"))
      (node (ref "U6") (pin "6") (pinfunction "CLSB_6") (pintype "output"))
    )
    (net (code "139") (name "Net-(U6-DEN)") (class "Default")
      (node (ref "R9") (pin "2") (pinfunction "2_2") (pintype "passive"))
      (node (ref "U6") (pin "2") (pinfunction "DEN_2") (pintype "bidirectional"))
    )
    (net (code "140") (name "Net-(U6-MPS_DUTY)") (class "Default")
      (node (ref "R11") (pin "2") (pinfunction "2_2") (pintype "passive"))
      (node (ref "U6") (pin "9") (pinfunction "MPS_DUTY_9") (pintype "input"))
    )
    (net (code "141") (name "Net-(U6-REF)") (class "Default")
      (node (ref "R14") (pin "2") (pinfunction "2_2") (pintype "passive"))
      (node (ref "U6") (pin "7") (pinfunction "REF_7") (pintype "power_in"))
    )
    (net (code "142") (name "Net-(U10-QH')") (class "Default")
      (node (ref "U10") (pin "9") (pinfunction "QH'_9") (pintype "output"))
      (node (ref "U9") (pin "14") (pinfunction "SER_14") (pintype "input"))
    )
    (net (code "143") (name "Net-(U10-SER)") (class "Default")
      (node (ref "U10") (pin "14") (pinfunction "SER_14") (pintype "input"))
      (node (ref "U11") (pin "9") (pinfunction "QH'_9") (pintype "output"))
    )
    (net (code "144") (name "Net-(U11-SER)") (class "Default")
      (node (ref "U11") (pin "14") (pinfunction "SER_14") (pintype "input"))
      (node (ref "U12") (pin "9") (pinfunction "QH'_9") (pintype "output"))
    )
    (net (code "145") (name "VPOE") (class "Default")
      (node (ref "C2") (pin "1") (pinfunction "1_1") (pintype "passive"))
      (node (ref "C5") (pin "1") (pinfunction "1_1") (pintype "passive"))
      (node (ref "C6") (pin "1") (pinfunction "1_1") (pintype "passive"))
      (node (ref "D2") (pin "1") (pinfunction "C_1") (pintype "passive"))
      (node (ref "J1") (pin "2") (pintype "passive"))
      (node (ref "R3") (pin "2") (pinfunction "2_2") (pintype "passive"))
      (node (ref "R9") (pin "1") (pinfunction "1_1") (pintype "passive"))
      (node (ref "U1") (pin "5") (pinfunction "IN_5") (pintype "power_in"))
      (node (ref "U6") (pin "1") (pinfunction "VDD_1") (pintype "power_in"))
      (node (ref "U7") (pin "5") (pinfunction "OUTP_5") (pintype "passive"))
      (node (ref "U7") (pin "6") (pinfunction "OUTP_6") (pintype "passive"))
      (node (ref "U7") (pin "7") (pinfunction "OUTP_7") (pintype "passive"))
      (node (ref "U7") (pin "8") (pinfunction "OUTP_8") (pintype "passive"))
      (node (ref "U8") (pin "5") (pinfunction "OUTP_5") (pintype "passive"))
      (node (ref "U8") (pin "6") (pinfunction "OUTP_6") (pintype "passive"))
      (node (ref "U8") (pin "7") (pinfunction "OUTP_7") (pintype "passive"))
      (node (ref "U8") (pin "8") (pinfunction "OUTP_8") (pintype "passive"))
    )
    (net (code "146") (name "unconnected-(U2-+5V-Pad54)") (class "Default")
      (node (ref "U2") (pin "54") (pinfunction "+5V_54") (pintype "passive"))
    )
    (net (code "147") (name "unconnected-(U2-3.3V-Pad50)") (class "Default")
      (node (ref "U2") (pin "50") (pinfunction "3.3V_50") (pintype "passive"))
    )
    (net (code "148") (name "unconnected-(U2-D+-Pad56)") (class "Default")
      (node (ref "U2") (pin "56") (pinfunction "D+_56") (pintype "passive"))
    )
    (net (code "149") (name "unconnected-(U2-D--Pad55)") (class "Default")
      (node (ref "U2") (pin "55") (pinfunction "D-_55") (pintype "passive"))
    )
    (net (code "150") (name "unconnected-(U2-ON{slash}OFF-Pad53)") (class "Default")
      (node (ref "U2") (pin "53") (pinfunction "ON/OFF_53") (pintype "passive"))
    )
    (net (code "151") (name "unconnected-(U2-PROGRAM-Pad52)") (class "Default")
      (node (ref "U2") (pin "52") (pinfunction "PROGRAM_52") (pintype "passive"))
    )
    (net (code "152") (name "unconnected-(U2-VBATT-Pad49)") (class "Default")
      (node (ref "U2") (pin "49") (pinfunction "VBATT_49") (pintype "passive"))
    )
    (net (code "153") (name "unconnected-(U2-VUSB-Pad59)") (class "Default")
      (node (ref "U2") (pin "59") (pinfunction "VUSB_59") (pintype "passive"))
    )
    (net (code "154") (name "unconnected-(U6-IRSHDL_EN-Pad16)") (class "Default")
      (node (ref "U6") (pin "16") (pinfunction "IRSHDL_EN_16") (pintype "input"))
    )
    (net (code "155") (name "unconnected-(U6-NC-Pad14)") (class "Default")
      (node (ref "U6") (pin "14") (pinfunction "NC_14") (pintype "passive"))
    )
    (net (code "156") (name "unconnected-(U6-NC-Pad15)") (class "Default")
      (node (ref "U6") (pin "15") (pinfunction "NC_15") (pintype "passive"))
    )
    (net (code "157") (name "unconnected-(U6-NC-Pad20)") (class "Default")
      (node (ref "U6") (pin "20") (pinfunction "NC_20") (pintype "passive"))
    )
    (net (code "158") (name "unconnected-(U6-~{AUTCLS}-Pad10)") (class "Default")
      (node (ref "U6") (pin "10") (pinfunction "~{AUTCLS}_10") (pintype "input"))
    )
    (net (code "159") (name "unconnected-(U9-QH'-Pad9)") (class "Default")
      (node (ref "U9") (pin "9") (pinfunction "QH'_9") (pintype "output"))
    )
  )
)
